# altera_digital_explorer.net
KiCad netlist of a schematic drawn in EAGLE
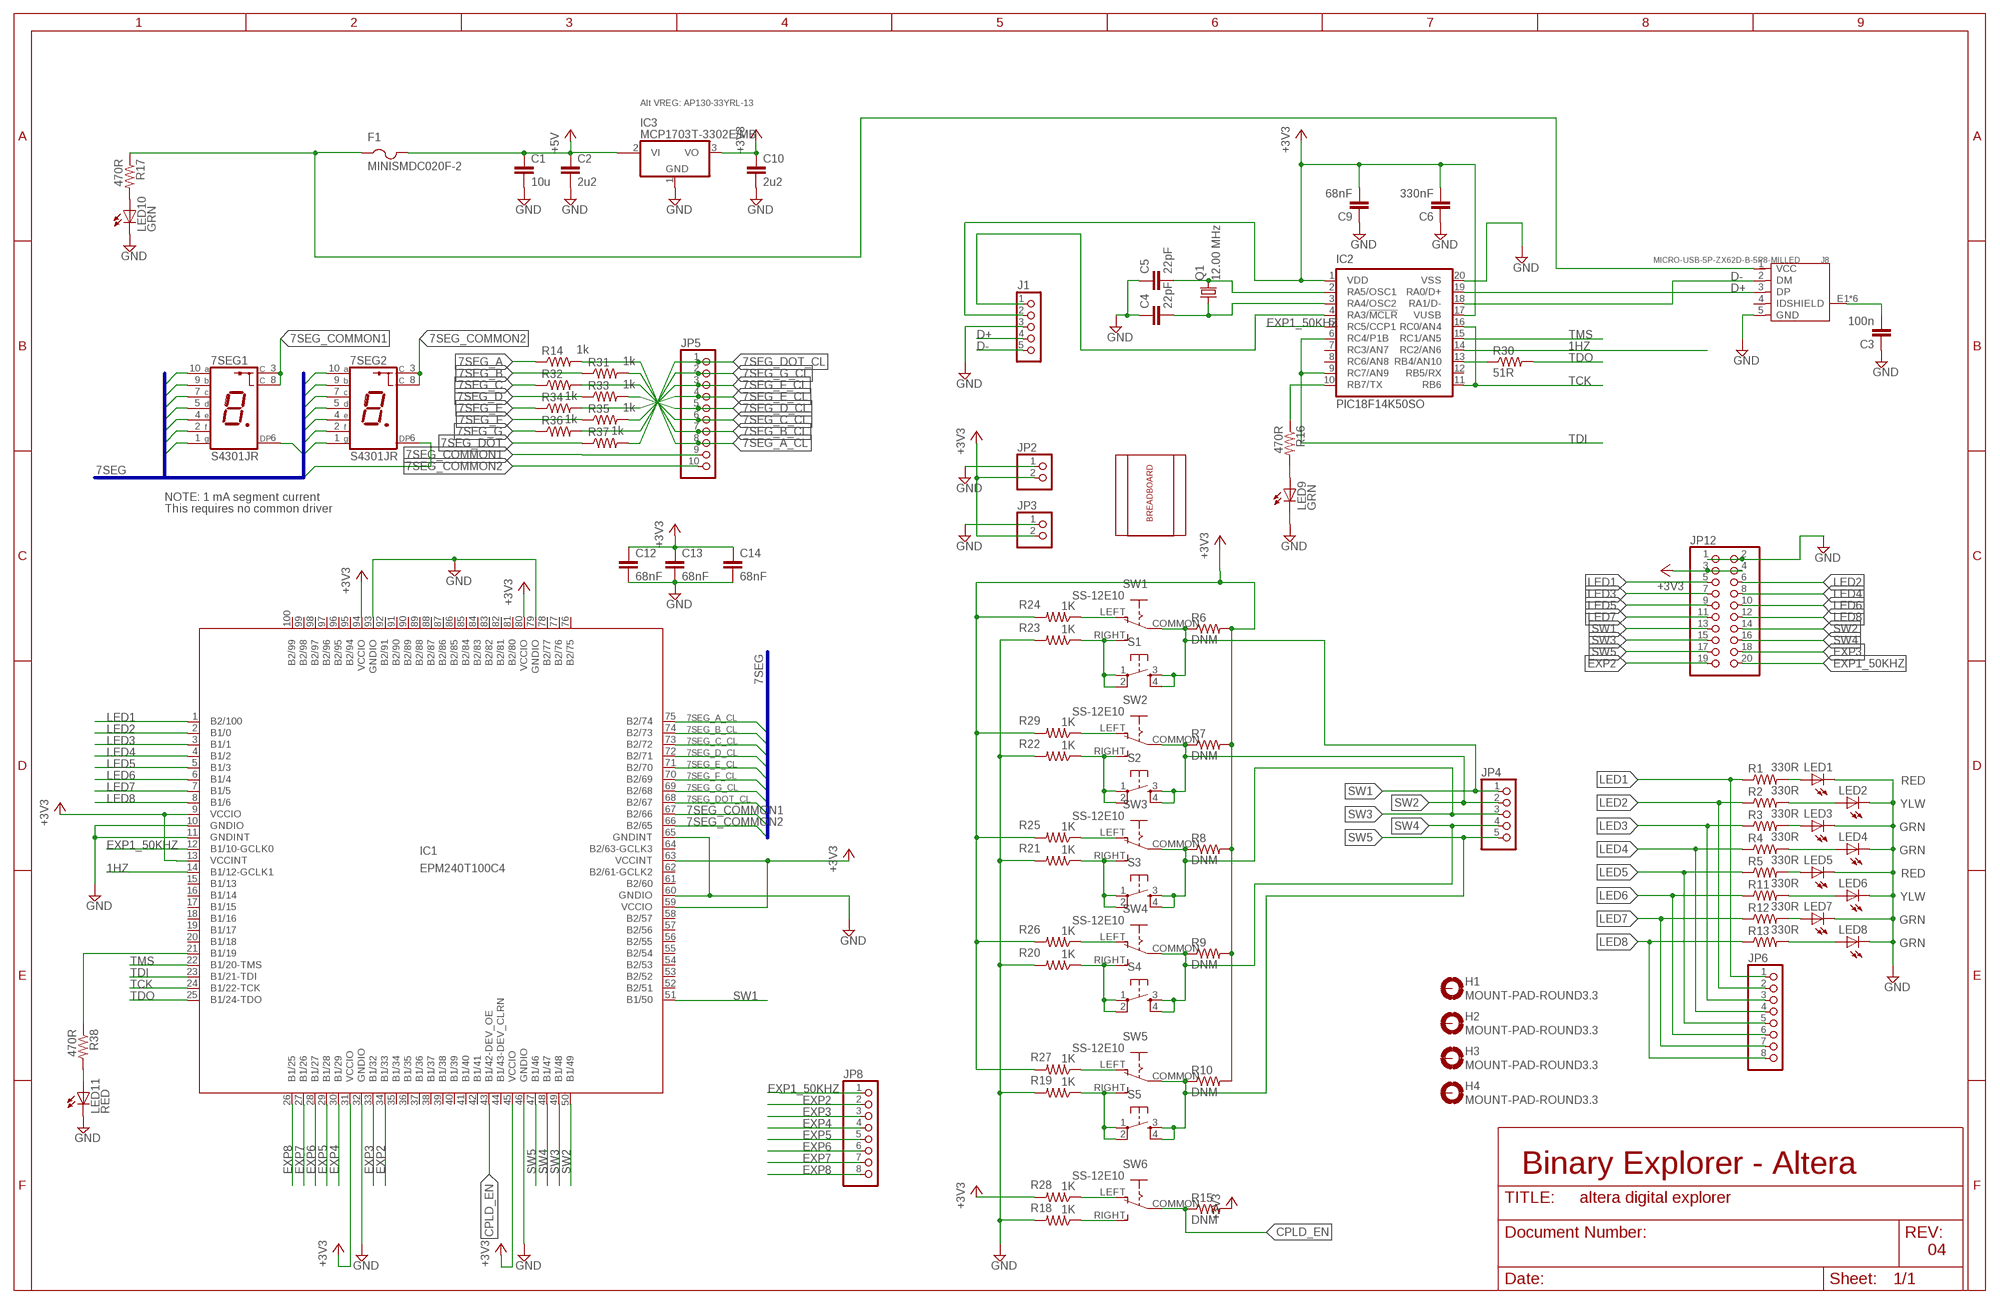
[diagram p0: schematic, sheet 1]

(export (version "E")
  (design (tool "Eeschema 10.0.6"))
  (components
    (comp (ref "7SEG1")
      (value "S4301JR")
      (footprint "eagle-import:S4301B")
      (libsource (lib "eagle-import") (part "S4301B"))
    )
    (comp (ref "7SEG2")
      (value "S4301JR")
      (footprint "eagle-import:S4301B")
      (libsource (lib "eagle-import") (part "S4301B"))
    )
    (comp (ref "C1")
      (value "10u")
      (footprint "eagle-import:C0805")
      (libsource (lib "eagle-import") (part "C-EUC0805"))
    )
    (comp (ref "C2")
      (value "2u2")
      (footprint "eagle-import:C0805")
      (libsource (lib "eagle-import") (part "C-EUC0805"))
    )
    (comp (ref "C3")
      (value "100n")
      (footprint "eagle-import:C0603")
      (libsource (lib "eagle-import") (part "C-EUC0603"))
    )
    (comp (ref "C4")
      (value "22pF")
      (footprint "eagle-import:C0603")
      (libsource (lib "eagle-import") (part "C-EUC0603"))
    )
    (comp (ref "C5")
      (value "22pF")
      (footprint "eagle-import:C0603")
      (libsource (lib "eagle-import") (part "C-EUC0603"))
    )
    (comp (ref "C6")
      (value "330nF")
      (footprint "eagle-import:C0603")
      (libsource (lib "eagle-import") (part "C-EUC0603"))
    )
    (comp (ref "C9")
      (value "68nF")
      (footprint "eagle-import:C0603")
      (libsource (lib "eagle-import") (part "C-EUC0603"))
    )
    (comp (ref "C10")
      (value "2u2")
      (footprint "eagle-import:C0805")
      (libsource (lib "eagle-import") (part "C-EUC0805"))
    )
    (comp (ref "C12")
      (value "68nF")
      (footprint "eagle-import:C0603")
      (libsource (lib "eagle-import") (part "resistor_C-EUC0603"))
    )
    (comp (ref "C13")
      (value "68nF")
      (footprint "eagle-import:C0603K")
      (libsource (lib "eagle-import") (part "resistor_C-EUC0603K"))
    )
    (comp (ref "C14")
      (value "68nF")
      (footprint "eagle-import:C0603")
      (libsource (lib "eagle-import") (part "resistor_C-EUC0603"))
    )
    (comp (ref "F1")
      (value "MINISMDC020F-2")
      (footprint "eagle-import:1812")
      (libsource (lib "eagle-import") (part "PTCFUSE-1812"))
    )
    (comp (ref "H1")
      (value "MOUNT-PAD-ROUND3.3")
      (footprint "eagle-import:3,3-PAD")
      (libsource (lib "eagle-import") (part "MOUNT-PAD-ROUND3.3"))
    )
    (comp (ref "H2")
      (value "MOUNT-PAD-ROUND3.3")
      (footprint "eagle-import:3,3-PAD")
      (libsource (lib "eagle-import") (part "MOUNT-PAD-ROUND3.3"))
    )
    (comp (ref "H3")
      (value "MOUNT-PAD-ROUND3.3")
      (footprint "eagle-import:3,3-PAD")
      (libsource (lib "eagle-import") (part "MOUNT-PAD-ROUND3.3"))
    )
    (comp (ref "H4")
      (value "MOUNT-PAD-ROUND3.3")
      (footprint "eagle-import:3,3-PAD")
      (libsource (lib "eagle-import") (part "MOUNT-PAD-ROUND3.3"))
    )
    (comp (ref "IC1")
      (value "EPM240T100C4")
      (footprint "eagle-import:TQFP100")
      (libsource (lib "eagle-import") (part "EPM240T100C4"))
    )
    (comp (ref "IC2")
      (value "PIC18F14K50SO")
      (footprint "eagle-import:SO20")
      (libsource (lib "eagle-import") (part "PIC18F14K50SO"))
    )
    (comp (ref "IC3")
      (value "MCP1703T-3302E/MB")
      (footprint "eagle-import:SOT89")
      (libsource (lib "eagle-import") (part "MCP1703MB33"))
    )
    (comp (ref "J1")
      (value "CON_HEADER_1X05-PTH")
      (footprint "eagle-import:M1X5")
      (libsource (lib "eagle-import") (part "CON_HEADER_1X05-PTH"))
    )
    (comp (ref "J8")
      (value "MICRO-USB-5P-ZX62D-B-5P8-MILLED")
      (footprint "eagle-import:B-SMD-5P-TH-MILLED")
      (fields (field (name "MPN") "ZX62D-B-5P8") (field (name "OC_DIGIKEY") "H11610CT-ND"))
      (libsource (lib "eagle-import") (part "MICRO-USB-5P-ZX62D-B-5P8-MILLED"))
    )
    (comp (ref "JP2")
      (value "PINHD-1X2")
      (footprint "eagle-import:1X02")
      (libsource (lib "eagle-import") (part "PINHD-1X2"))
    )
    (comp (ref "JP3")
      (value "PINHD-1X2")
      (footprint "eagle-import:1X02")
      (libsource (lib "eagle-import") (part "PINHD-1X2"))
    )
    (comp (ref "JP4")
      (value "PINHD-1X5")
      (footprint "eagle-import:1X05")
      (libsource (lib "eagle-import") (part "PINHD-1X5"))
    )
    (comp (ref "JP5")
      (value "PINHD-1X10")
      (footprint "eagle-import:1X10")
      (libsource (lib "eagle-import") (part "PINHD-1X10"))
    )
    (comp (ref "JP6")
      (value "PINHD-1X8")
      (footprint "eagle-import:1X08")
      (libsource (lib "eagle-import") (part "PINHD-1X8"))
    )
    (comp (ref "JP8")
      (value "PINHD-1X8")
      (footprint "eagle-import:1X08")
      (libsource (lib "eagle-import") (part "PINHD-1X8"))
    )
    (comp (ref "JP12")
      (value "PINHD-2X10")
      (footprint "eagle-import:2X10")
      (libsource (lib "eagle-import") (part "PINHD-2X10"))
    )
    (comp (ref "LED1")
      (value "RED")
      (footprint "eagle-import:CHIP-LED0805")
      (libsource (lib "eagle-import") (part "LEDCHIP-LED0805"))
    )
    (comp (ref "LED2")
      (value "YLW")
      (footprint "eagle-import:CHIP-LED0805")
      (libsource (lib "eagle-import") (part "LEDCHIP-LED0805"))
    )
    (comp (ref "LED3")
      (value "GRN")
      (footprint "eagle-import:CHIP-LED0805")
      (libsource (lib "eagle-import") (part "LEDCHIP-LED0805"))
    )
    (comp (ref "LED4")
      (value "GRN")
      (footprint "eagle-import:CHIP-LED0805")
      (libsource (lib "eagle-import") (part "LEDCHIP-LED0805"))
    )
    (comp (ref "LED5")
      (value "RED")
      (footprint "eagle-import:CHIP-LED0805")
      (libsource (lib "eagle-import") (part "LEDCHIP-LED0805"))
    )
    (comp (ref "LED6")
      (value "YLW")
      (footprint "eagle-import:CHIP-LED0805")
      (libsource (lib "eagle-import") (part "LEDCHIP-LED0805"))
    )
    (comp (ref "LED7")
      (value "GRN")
      (footprint "eagle-import:CHIP-LED0805")
      (libsource (lib "eagle-import") (part "LEDCHIP-LED0805"))
    )
    (comp (ref "LED8")
      (value "GRN")
      (footprint "eagle-import:CHIP-LED0805")
      (libsource (lib "eagle-import") (part "LEDCHIP-LED0805"))
    )
    (comp (ref "LED9")
      (value "GRN")
      (footprint "eagle-import:CHIP-LED0805")
      (libsource (lib "eagle-import") (part "LEDCHIP-LED0805"))
    )
    (comp (ref "LED10")
      (value "GRN")
      (footprint "eagle-import:CHIP-LED0805")
      (libsource (lib "eagle-import") (part "LEDCHIP-LED0805"))
    )
    (comp (ref "LED11")
      (value "RED")
      (footprint "eagle-import:CHIP-LED0805")
      (libsource (lib "eagle-import") (part "LEDCHIP-LED0805"))
    )
    (comp (ref "Q1")
      (value "12.00 MHz")
      (footprint "eagle-import:HC49UP")
      (fields (field (name "MPN") "ATS080BSM-1"))
      (libsource (lib "eagle-import") (part "CRYSTALHC49UP"))
    )
    (comp (ref "R1")
      (value "330R")
      (footprint "eagle-import:R0603")
      (libsource (lib "eagle-import") (part "resistor_R-US_R0603"))
    )
    (comp (ref "R2")
      (value "330R")
      (footprint "eagle-import:R0603")
      (libsource (lib "eagle-import") (part "resistor_R-US_R0603"))
    )
    (comp (ref "R3")
      (value "330R")
      (footprint "eagle-import:R0603")
      (libsource (lib "eagle-import") (part "resistor_R-US_R0603"))
    )
    (comp (ref "R4")
      (value "330R")
      (footprint "eagle-import:R0603")
      (libsource (lib "eagle-import") (part "resistor_R-US_R0603"))
    )
    (comp (ref "R5")
      (value "330R")
      (footprint "eagle-import:R0603")
      (libsource (lib "eagle-import") (part "resistor_R-US_R0603"))
    )
    (comp (ref "R6")
      (value "DNM")
      (footprint "eagle-import:R0603")
      (libsource (lib "eagle-import") (part "resistor_R-US_R0603"))
    )
    (comp (ref "R7")
      (value "DNM")
      (footprint "eagle-import:R0603")
      (libsource (lib "eagle-import") (part "resistor_R-US_R0603"))
    )
    (comp (ref "R8")
      (value "DNM")
      (footprint "eagle-import:R0603")
      (libsource (lib "eagle-import") (part "resistor_R-US_R0603"))
    )
    (comp (ref "R9")
      (value "DNM")
      (footprint "eagle-import:R0603")
      (libsource (lib "eagle-import") (part "resistor_R-US_R0603"))
    )
    (comp (ref "R10")
      (value "DNM")
      (footprint "eagle-import:R0603")
      (libsource (lib "eagle-import") (part "resistor_R-US_R0603"))
    )
    (comp (ref "R11")
      (value "330R")
      (footprint "eagle-import:R0603")
      (libsource (lib "eagle-import") (part "resistor_R-US_R0603"))
    )
    (comp (ref "R12")
      (value "330R")
      (footprint "eagle-import:R0603")
      (libsource (lib "eagle-import") (part "resistor_R-US_R0603"))
    )
    (comp (ref "R13")
      (value "330R")
      (footprint "eagle-import:R0603")
      (libsource (lib "eagle-import") (part "resistor_R-US_R0603"))
    )
    (comp (ref "R14")
      (value "1k")
      (footprint "eagle-import:R0603")
      (libsource (lib "eagle-import") (part "resistor_R-US_R0603"))
    )
    (comp (ref "R15")
      (value "DNM")
      (footprint "eagle-import:R0603")
      (libsource (lib "eagle-import") (part "resistor_R-US_R0603"))
    )
    (comp (ref "R16")
      (value "470R")
      (footprint "eagle-import:R0603")
      (libsource (lib "eagle-import") (part "R-US_R0603"))
    )
    (comp (ref "R17")
      (value "470R")
      (footprint "eagle-import:R0603")
      (libsource (lib "eagle-import") (part "R-US_R0603"))
    )
    (comp (ref "R18")
      (value "1K")
      (footprint "eagle-import:R0603")
      (libsource (lib "eagle-import") (part "resistor_R-US_R0603"))
    )
    (comp (ref "R19")
      (value "1K")
      (footprint "eagle-import:R0603")
      (libsource (lib "eagle-import") (part "resistor_R-US_R0603"))
    )
    (comp (ref "R20")
      (value "1K")
      (footprint "eagle-import:R0603")
      (libsource (lib "eagle-import") (part "resistor_R-US_R0603"))
    )
    (comp (ref "R21")
      (value "1K")
      (footprint "eagle-import:R0603")
      (libsource (lib "eagle-import") (part "resistor_R-US_R0603"))
    )
    (comp (ref "R22")
      (value "1K")
      (footprint "eagle-import:R0603")
      (libsource (lib "eagle-import") (part "resistor_R-US_R0603"))
    )
    (comp (ref "R23")
      (value "1K")
      (footprint "eagle-import:R0603")
      (libsource (lib "eagle-import") (part "resistor_R-US_R0603"))
    )
    (comp (ref "R24")
      (value "1K")
      (footprint "eagle-import:R0603")
      (libsource (lib "eagle-import") (part "resistor_R-US_R0603"))
    )
    (comp (ref "R25")
      (value "1K")
      (footprint "eagle-import:R0603")
      (libsource (lib "eagle-import") (part "resistor_R-US_R0603"))
    )
    (comp (ref "R26")
      (value "1K")
      (footprint "eagle-import:R0603")
      (libsource (lib "eagle-import") (part "resistor_R-US_R0603"))
    )
    (comp (ref "R27")
      (value "1K")
      (footprint "eagle-import:R0603")
      (libsource (lib "eagle-import") (part "resistor_R-US_R0603"))
    )
    (comp (ref "R28")
      (value "1K")
      (footprint "eagle-import:R0603")
      (libsource (lib "eagle-import") (part "resistor_R-US_R0603"))
    )
    (comp (ref "R29")
      (value "1K")
      (footprint "eagle-import:R0603")
      (libsource (lib "eagle-import") (part "resistor_R-US_R0603"))
    )
    (comp (ref "R30")
      (value "51R")
      (footprint "eagle-import:R0603")
      (libsource (lib "eagle-import") (part "R-US_R0603"))
    )
    (comp (ref "R31")
      (value "1k")
      (footprint "eagle-import:R0603")
      (libsource (lib "eagle-import") (part "resistor_R-US_R0603"))
    )
    (comp (ref "R32")
      (value "R-US_R0603")
      (footprint "eagle-import:R0603")
      (libsource (lib "eagle-import") (part "resistor_R-US_R0603"))
    )
    (comp (ref "R33")
      (value "1k")
      (footprint "eagle-import:R0603")
      (libsource (lib "eagle-import") (part "resistor_R-US_R0603"))
    )
    (comp (ref "R34")
      (value "1k")
      (footprint "eagle-import:R0603")
      (libsource (lib "eagle-import") (part "resistor_R-US_R0603"))
    )
    (comp (ref "R35")
      (value "1k")
      (footprint "eagle-import:R0603")
      (libsource (lib "eagle-import") (part "resistor_R-US_R0603"))
    )
    (comp (ref "R36")
      (value "1k")
      (footprint "eagle-import:R0603")
      (libsource (lib "eagle-import") (part "resistor_R-US_R0603"))
    )
    (comp (ref "R37")
      (value "1k")
      (footprint "eagle-import:R0603")
      (libsource (lib "eagle-import") (part "resistor_R-US_R0603"))
    )
    (comp (ref "R38")
      (value "470R")
      (footprint "eagle-import:R0603")
      (libsource (lib "eagle-import") (part "R-US_R0603"))
    )
    (comp (ref "S1")
      (value "TAC_SWITCHPTH")
      (footprint "eagle-import:TACTILE-PTH")
      (libsource (lib "eagle-import") (part "TAC_SWITCHPTH"))
    )
    (comp (ref "S2")
      (value "TAC_SWITCHPTH")
      (footprint "eagle-import:TACTILE-PTH")
      (libsource (lib "eagle-import") (part "TAC_SWITCHPTH"))
    )
    (comp (ref "S3")
      (value "TAC_SWITCHPTH")
      (footprint "eagle-import:TACTILE-PTH")
      (libsource (lib "eagle-import") (part "TAC_SWITCHPTH"))
    )
    (comp (ref "S4")
      (value "TAC_SWITCHPTH")
      (footprint "eagle-import:TACTILE-PTH")
      (libsource (lib "eagle-import") (part "TAC_SWITCHPTH"))
    )
    (comp (ref "S5")
      (value "TAC_SWITCHPTH")
      (footprint "eagle-import:TACTILE-PTH")
      (libsource (lib "eagle-import") (part "TAC_SWITCHPTH"))
    )
    (comp (ref "SW1")
      (value "SS-12E10")
      (footprint "eagle-import:SS-12E10")
      (libsource (lib "eagle-import") (part "SS-12E10"))
    )
    (comp (ref "SW2")
      (value "SS-12E10")
      (footprint "eagle-import:SS-12E10")
      (libsource (lib "eagle-import") (part "SS-12E10"))
    )
    (comp (ref "SW3")
      (value "SS-12E10")
      (footprint "eagle-import:SS-12E10")
      (libsource (lib "eagle-import") (part "SS-12E10"))
    )
    (comp (ref "SW4")
      (value "SS-12E10")
      (footprint "eagle-import:SS-12E10")
      (libsource (lib "eagle-import") (part "SS-12E10"))
    )
    (comp (ref "SW5")
      (value "SS-12E10")
      (footprint "eagle-import:SS-12E10")
      (libsource (lib "eagle-import") (part "SS-12E10"))
    )
    (comp (ref "SW6")
      (value "SS-12E10")
      (footprint "eagle-import:SS-12E10")
      (libsource (lib "eagle-import") (part "SS-12E10"))
    )
    (comp (ref "U$1")
      (value "BB-400TP")
      (footprint "eagle-import:BB-400TP")
      (libsource (lib "eagle-import") (part "BB-400TP"))
    )
  )
  (nets
    (net (code "1") (name "+3V3") (class "Default")
      (node (ref "C10") (pin "1") (pinfunction "1_1") (pintype "passive"))
      (node (ref "C12") (pin "1") (pinfunction "1_1") (pintype "passive"))
      (node (ref "C13") (pin "1") (pinfunction "1_1") (pintype "passive"))
      (node (ref "C14") (pin "1") (pinfunction "1_1") (pintype "passive"))
      (node (ref "C6") (pin "2") (pinfunction "2_2") (pintype "passive"))
      (node (ref "C9") (pin "2") (pinfunction "2_2") (pintype "passive"))
      (node (ref "IC1") (pin "13") (pinfunction "VCCINT_13") (pintype "power_in"))
      (node (ref "IC1") (pin "31") (pinfunction "VCCIO_31") (pintype "power_in"))
      (node (ref "IC1") (pin "45") (pinfunction "VCCIO_45") (pintype "power_in"))
      (node (ref "IC1") (pin "59") (pinfunction "VCCIO_59") (pintype "power_in"))
      (node (ref "IC1") (pin "63") (pinfunction "VCCINT_63") (pintype "power_in"))
      (node (ref "IC1") (pin "80") (pinfunction "VCCIO_80") (pintype "power_in"))
      (node (ref "IC1") (pin "9") (pinfunction "VCCIO_9") (pintype "power_in"))
      (node (ref "IC1") (pin "94") (pinfunction "VCCIO_94") (pintype "power_in"))
      (node (ref "IC2") (pin "1") (pinfunction "VDD_1") (pintype "power_in"))
      (node (ref "IC2") (pin "17") (pinfunction "VUSB_17") (pintype "bidirectional"))
      (node (ref "IC3") (pin "3") (pinfunction "VO_3") (pintype "passive"))
      (node (ref "J1") (pin "2") (pinfunction "2_2") (pintype "bidirectional"))
      (node (ref "JP12") (pin "3") (pinfunction "3_3") (pintype "passive"))
      (node (ref "JP12") (pin "4") (pinfunction "4_4") (pintype "passive"))
      (node (ref "JP2") (pin "2") (pinfunction "2_2") (pintype "passive"))
      (node (ref "JP3") (pin "2") (pinfunction "2_2") (pintype "passive"))
      (node (ref "R10") (pin "2") (pinfunction "2_2") (pintype "passive"))
      (node (ref "R15") (pin "2") (pinfunction "2_2") (pintype "passive"))
      (node (ref "R24") (pin "2") (pinfunction "2_2") (pintype "passive"))
      (node (ref "R25") (pin "2") (pinfunction "2_2") (pintype "passive"))
      (node (ref "R26") (pin "2") (pinfunction "2_2") (pintype "passive"))
      (node (ref "R27") (pin "2") (pinfunction "2_2") (pintype "passive"))
      (node (ref "R28") (pin "2") (pinfunction "2_2") (pintype "passive"))
      (node (ref "R29") (pin "2") (pinfunction "2_2") (pintype "passive"))
      (node (ref "R6") (pin "2") (pinfunction "2_2") (pintype "passive"))
      (node (ref "R7") (pin "2") (pinfunction "2_2") (pintype "passive"))
      (node (ref "R8") (pin "2") (pinfunction "2_2") (pintype "passive"))
      (node (ref "R9") (pin "2") (pinfunction "2_2") (pintype "passive"))
    )
    (net (code "2") (name "+5V") (class "Default")
      (node (ref "C1") (pin "1") (pinfunction "1_1") (pintype "passive"))
      (node (ref "C2") (pin "1") (pinfunction "1_1") (pintype "passive"))
      (node (ref "F1") (pin "2") (pinfunction "2_2") (pintype "passive"))
      (node (ref "IC3") (pin "2@1") (pinfunction "VI1_2@1") (pintype "input"))
    )
    (net (code "3") (name "/1HZ") (class "Default")
      (node (ref "IC1") (pin "14") (pinfunction "B1/12-GCLK1_14") (pintype "bidirectional"))
      (node (ref "IC2") (pin "14") (pinfunction "RC2/AN6_14") (pintype "bidirectional"))
    )
    (net (code "4") (name "/D+") (class "Default")
      (node (ref "IC2") (pin "19") (pinfunction "RA0/D+_19") (pintype "bidirectional"))
      (node (ref "J1") (pin "4") (pinfunction "4_4") (pintype "bidirectional"))
      (node (ref "J8") (pin "3") (pinfunction "DP_3") (pintype "bidirectional"))
    )
    (net (code "5") (name "/D-") (class "Default")
      (node (ref "IC2") (pin "18") (pinfunction "RA1/D-_18") (pintype "bidirectional"))
      (node (ref "J1") (pin "5") (pinfunction "5_5") (pintype "bidirectional"))
      (node (ref "J8") (pin "2") (pinfunction "DM_2") (pintype "bidirectional"))
    )
    (net (code "6") (name "/EXP4") (class "Default")
      (node (ref "IC1") (pin "30") (pinfunction "B1/29_30") (pintype "bidirectional"))
      (node (ref "JP8") (pin "4") (pinfunction "4_4") (pintype "passive"))
    )
    (net (code "7") (name "/EXP5") (class "Default")
      (node (ref "IC1") (pin "29") (pinfunction "B1/28_29") (pintype "bidirectional"))
      (node (ref "JP8") (pin "5") (pinfunction "5_5") (pintype "passive"))
    )
    (net (code "8") (name "/EXP6") (class "Default")
      (node (ref "IC1") (pin "28") (pinfunction "B1/27_28") (pintype "bidirectional"))
      (node (ref "JP8") (pin "6") (pinfunction "6_6") (pintype "passive"))
    )
    (net (code "9") (name "/EXP7") (class "Default")
      (node (ref "IC1") (pin "27") (pinfunction "B1/26_27") (pintype "bidirectional"))
      (node (ref "JP8") (pin "7") (pinfunction "7_7") (pintype "passive"))
    )
    (net (code "10") (name "/EXP8") (class "Default")
      (node (ref "IC1") (pin "26") (pinfunction "B1/25_26") (pintype "bidirectional"))
      (node (ref "JP8") (pin "8") (pinfunction "8_8") (pintype "passive"))
    )
    (net (code "11") (name "/TCK") (class "Default")
      (node (ref "IC1") (pin "24") (pinfunction "B1/22-TCK_24") (pintype "input"))
      (node (ref "IC2") (pin "11") (pinfunction "RB6_11") (pintype "bidirectional"))
      (node (ref "IC2") (pin "16") (pinfunction "RC0/AN4_16") (pintype "bidirectional"))
    )
    (net (code "12") (name "/TDI") (class "Default")
      (node (ref "IC1") (pin "23") (pinfunction "B1/21-TDI_23") (pintype "input"))
      (node (ref "IC2") (pin "6") (pinfunction "RC4/P1B_6") (pintype "bidirectional"))
      (node (ref "IC2") (pin "9") (pinfunction "RC7/AN9_9") (pintype "bidirectional"))
    )
    (net (code "13") (name "/TDO") (class "Default")
      (node (ref "IC1") (pin "25") (pinfunction "B1/24-TDO_25") (pintype "output"))
      (node (ref "R30") (pin "2") (pinfunction "2_2") (pintype "passive"))
    )
    (net (code "14") (name "/TMS") (class "Default")
      (node (ref "IC1") (pin "22") (pinfunction "B1/20-TMS_22") (pintype "input"))
      (node (ref "IC2") (pin "15") (pinfunction "RC1/AN5_15") (pintype "bidirectional"))
    )
    (net (code "15") (name "7SEG_A") (class "Default")
      (node (ref "7SEG1") (pin "10") (pinfunction "A_10") (pintype "passive"))
      (node (ref "7SEG2") (pin "10") (pinfunction "A_10") (pintype "passive"))
      (node (ref "R14") (pin "1") (pinfunction "1_1") (pintype "passive"))
    )
    (net (code "16") (name "7SEG_A_CL") (class "Default")
      (node (ref "IC1") (pin "75") (pinfunction "B2/74_75") (pintype "bidirectional"))
      (node (ref "JP5") (pin "8") (pinfunction "8_8") (pintype "passive"))
      (node (ref "R14") (pin "2") (pinfunction "2_2") (pintype "passive"))
    )
    (net (code "17") (name "7SEG_B") (class "Default")
      (node (ref "7SEG1") (pin "9") (pinfunction "B_9") (pintype "passive"))
      (node (ref "7SEG2") (pin "9") (pinfunction "B_9") (pintype "passive"))
      (node (ref "R31") (pin "1") (pinfunction "1_1") (pintype "passive"))
    )
    (net (code "18") (name "7SEG_B_CL") (class "Default")
      (node (ref "IC1") (pin "74") (pinfunction "B2/73_74") (pintype "bidirectional"))
      (node (ref "JP5") (pin "7") (pinfunction "7_7") (pintype "passive"))
      (node (ref "R31") (pin "2") (pinfunction "2_2") (pintype "passive"))
    )
    (net (code "19") (name "7SEG_C") (class "Default")
      (node (ref "7SEG1") (pin "7") (pinfunction "C_7") (pintype "passive"))
      (node (ref "7SEG2") (pin "7") (pinfunction "C_7") (pintype "passive"))
      (node (ref "R32") (pin "1") (pinfunction "1_1") (pintype "passive"))
    )
    (net (code "20") (name "7SEG_COMMON1") (class "Default")
      (node (ref "7SEG1") (pin "3") (pinfunction "C_3") (pintype "passive"))
      (node (ref "7SEG1") (pin "8") (pinfunction "C_8") (pintype "passive"))
      (node (ref "IC1") (pin "67") (pinfunction "B2/66_67") (pintype "bidirectional"))
      (node (ref "JP5") (pin "9") (pinfunction "9_9") (pintype "passive"))
    )
    (net (code "21") (name "7SEG_COMMON2") (class "Default")
      (node (ref "7SEG2") (pin "3") (pinfunction "C_3") (pintype "passive"))
      (node (ref "7SEG2") (pin "8") (pinfunction "C_8") (pintype "passive"))
      (node (ref "IC1") (pin "66") (pinfunction "B2/65_66") (pintype "bidirectional"))
      (node (ref "JP5") (pin "10") (pinfunction "10_10") (pintype "passive"))
    )
    (net (code "22") (name "7SEG_C_CL") (class "Default")
      (node (ref "IC1") (pin "73") (pinfunction "B2/72_73") (pintype "bidirectional"))
      (node (ref "JP5") (pin "6") (pinfunction "6_6") (pintype "passive"))
      (node (ref "R32") (pin "2") (pinfunction "2_2") (pintype "passive"))
    )
    (net (code "23") (name "7SEG_D") (class "Default")
      (node (ref "7SEG1") (pin "5") (pinfunction "D_5") (pintype "passive"))
      (node (ref "7SEG2") (pin "5") (pinfunction "D_5") (pintype "passive"))
      (node (ref "R33") (pin "1") (pinfunction "1_1") (pintype "passive"))
    )
    (net (code "24") (name "7SEG_DOT") (class "Default")
      (node (ref "7SEG1") (pin "6") (pinfunction "DP_6") (pintype "passive"))
      (node (ref "7SEG2") (pin "6") (pinfunction "DP_6") (pintype "passive"))
      (node (ref "R37") (pin "1") (pinfunction "1_1") (pintype "passive"))
    )
    (net (code "25") (name "7SEG_DOT_CL") (class "Default")
      (node (ref "IC1") (pin "68") (pinfunction "B2/67_68") (pintype "bidirectional"))
      (node (ref "JP5") (pin "1") (pinfunction "1_1") (pintype "passive"))
      (node (ref "R37") (pin "2") (pinfunction "2_2") (pintype "passive"))
    )
    (net (code "26") (name "7SEG_D_CL") (class "Default")
      (node (ref "IC1") (pin "72") (pinfunction "B2/71_72") (pintype "bidirectional"))
      (node (ref "JP5") (pin "5") (pinfunction "5_5") (pintype "passive"))
      (node (ref "R33") (pin "2") (pinfunction "2_2") (pintype "passive"))
    )
    (net (code "27") (name "7SEG_E") (class "Default")
      (node (ref "7SEG1") (pin "4") (pinfunction "E_4") (pintype "passive"))
      (node (ref "7SEG2") (pin "4") (pinfunction "E_4") (pintype "passive"))
      (node (ref "R34") (pin "1") (pinfunction "1_1") (pintype "passive"))
    )
    (net (code "28") (name "7SEG_E_CL") (class "Default")
      (node (ref "IC1") (pin "71") (pinfunction "B2/70_71") (pintype "bidirectional"))
      (node (ref "JP5") (pin "4") (pinfunction "4_4") (pintype "passive"))
      (node (ref "R34") (pin "2") (pinfunction "2_2") (pintype "passive"))
    )
    (net (code "29") (name "7SEG_F") (class "Default")
      (node (ref "7SEG1") (pin "2") (pinfunction "F_2") (pintype "passive"))
      (node (ref "7SEG2") (pin "2") (pinfunction "F_2") (pintype "passive"))
      (node (ref "R35") (pin "1") (pinfunction "1_1") (pintype "passive"))
    )
    (net (code "30") (name "7SEG_F_CL") (class "Default")
      (node (ref "IC1") (pin "70") (pinfunction "B2/69_70") (pintype "bidirectional"))
      (node (ref "JP5") (pin "3") (pinfunction "3_3") (pintype "passive"))
      (node (ref "R35") (pin "2") (pinfunction "2_2") (pintype "passive"))
    )
    (net (code "31") (name "7SEG_G") (class "Default")
      (node (ref "7SEG1") (pin "1") (pinfunction "G_1") (pintype "passive"))
      (node (ref "7SEG2") (pin "1") (pinfunction "G_1") (pintype "passive"))
      (node (ref "R36") (pin "1") (pinfunction "1_1") (pintype "passive"))
    )
    (net (code "32") (name "7SEG_G_CL") (class "Default")
      (node (ref "IC1") (pin "69") (pinfunction "B2/68_69") (pintype "bidirectional"))
      (node (ref "JP5") (pin "2") (pinfunction "2_2") (pintype "passive"))
      (node (ref "R36") (pin "2") (pinfunction "2_2") (pintype "passive"))
    )
    (net (code "33") (name "CPLD_EN") (class "Default")
      (node (ref "IC1") (pin "43") (pinfunction "B1/42-DEV_OE_43") (pintype "bidirectional"))
      (node (ref "R15") (pin "1") (pinfunction "1_1") (pintype "passive"))
      (node (ref "SW6") (pin "COMMON") (pinfunction "P_COMMON") (pintype "passive"))
    )
    (net (code "34") (name "EXP1_50KHZ") (class "Default")
      (node (ref "IC1") (pin "12") (pinfunction "B1/10-GCLK0_12") (pintype "bidirectional"))
      (node (ref "IC2") (pin "5") (pinfunction "RC5/CCP1_5") (pintype "bidirectional"))
      (node (ref "JP12") (pin "20") (pinfunction "20_20") (pintype "passive"))
      (node (ref "JP8") (pin "1") (pinfunction "1_1") (pintype "passive"))
    )
    (net (code "35") (name "EXP2") (class "Default")
      (node (ref "IC1") (pin "34") (pinfunction "B1/33_34") (pintype "bidirectional"))
      (node (ref "JP12") (pin "19") (pinfunction "19_19") (pintype "passive"))
      (node (ref "JP8") (pin "2") (pinfunction "2_2") (pintype "passive"))
    )
    (net (code "36") (name "EXP3") (class "Default")
      (node (ref "IC1") (pin "33") (pinfunction "B1/32_33") (pintype "bidirectional"))
      (node (ref "JP12") (pin "18") (pinfunction "18_18") (pintype "passive"))
      (node (ref "JP8") (pin "3") (pinfunction "3_3") (pintype "passive"))
    )
    (net (code "37") (name "GND") (class "Default")
      (node (ref "C1") (pin "2") (pinfunction "2_2") (pintype "passive"))
      (node (ref "C10") (pin "2") (pinfunction "2_2") (pintype "passive"))
      (node (ref "C12") (pin "2") (pinfunction "2_2") (pintype "passive"))
      (node (ref "C13") (pin "2") (pinfunction "2_2") (pintype "passive"))
      (node (ref "C14") (pin "2") (pinfunction "2_2") (pintype "passive"))
      (node (ref "C2") (pin "2") (pinfunction "2_2") (pintype "passive"))
      (node (ref "C3") (pin "1") (pinfunction "1_1") (pintype "passive"))
      (node (ref "C4") (pin "1") (pinfunction "1_1") (pintype "passive"))
      (node (ref "C5") (pin "1") (pinfunction "1_1") (pintype "passive"))
      (node (ref "C6") (pin "1") (pinfunction "1_1") (pintype "passive"))
      (node (ref "C9") (pin "1") (pinfunction "1_1") (pintype "passive"))
      (node (ref "IC1") (pin "10") (pinfunction "GNDIO_10") (pintype "power_in"))
      (node (ref "IC1") (pin "11") (pinfunction "GNDINT_11") (pintype "power_in"))
      (node (ref "IC1") (pin "32") (pinfunction "GNDIO_32") (pintype "power_in"))
      (node (ref "IC1") (pin "46") (pinfunction "GNDIO_46") (pintype "power_in"))
      (node (ref "IC1") (pin "60") (pinfunction "GNDIO_60") (pintype "power_in"))
      (node (ref "IC1") (pin "65") (pinfunction "GNDINT_65") (pintype "power_in"))
      (node (ref "IC1") (pin "79") (pinfunction "GNDIO_79") (pintype "power_in"))
      (node (ref "IC1") (pin "93") (pinfunction "GNDIO_93") (pintype "power_in"))
      (node (ref "IC2") (pin "20") (pinfunction "VSS_20") (pintype "power_in"))
      (node (ref "IC3") (pin "1") (pinfunction "GND_1") (pintype "passive"))
      (node (ref "J1") (pin "3") (pinfunction "3_3") (pintype "bidirectional"))
      (node (ref "J8") (pin "5") (pinfunction "GND_5") (pintype "bidirectional"))
      (node (ref "JP12") (pin "1") (pinfunction "1_1") (pintype "passive"))
      (node (ref "JP12") (pin "2") (pinfunction "2_2") (pintype "passive"))
      (node (ref "JP2") (pin "1") (pinfunction "1_1") (pintype "passive"))
      (node (ref "JP3") (pin "1") (pinfunction "1_1") (pintype "passive"))
      (node (ref "LED1") (pin "C") (pinfunction "C_C") (pintype "passive"))
      (node (ref "LED10") (pin "C") (pinfunction "C_C") (pintype "passive"))
      (node (ref "LED11") (pin "C") (pinfunction "C_C") (pintype "passive"))
      (node (ref "LED2") (pin "C") (pinfunction "C_C") (pintype "passive"))
      (node (ref "LED3") (pin "C") (pinfunction "C_C") (pintype "passive"))
      (node (ref "LED4") (pin "C") (pinfunction "C_C") (pintype "passive"))
      (node (ref "LED5") (pin "C") (pinfunction "C_C") (pintype "passive"))
      (node (ref "LED6") (pin "C") (pinfunction "C_C") (pintype "passive"))
      (node (ref "LED7") (pin "C") (pinfunction "C_C") (pintype "passive"))
      (node (ref "LED8") (pin "C") (pinfunction "C_C") (pintype "passive"))
      (node (ref "LED9") (pin "C") (pinfunction "C_C") (pintype "passive"))
      (node (ref "R18") (pin "2") (pinfunction "2_2") (pintype "passive"))
      (node (ref "R19") (pin "2") (pinfunction "2_2") (pintype "passive"))
      (node (ref "R20") (pin "2") (pinfunction "2_2") (pintype "passive"))
      (node (ref "R21") (pin "2") (pinfunction "2_2") (pintype "passive"))
      (node (ref "R22") (pin "2") (pinfunction "2_2") (pintype "passive"))
      (node (ref "R23") (pin "2") (pinfunction "2_2") (pintype "passive"))
    )
    (net (code "38") (name "LED1") (class "Default")
      (node (ref "IC1") (pin "1") (pinfunction "B2/100_1") (pintype "bidirectional"))
      (node (ref "JP12") (pin "5") (pinfunction "5_5") (pintype "passive"))
      (node (ref "JP6") (pin "1") (pinfunction "1_1") (pintype "passive"))
      (node (ref "R1") (pin "1") (pinfunction "1_1") (pintype "passive"))
    )
    (net (code "39") (name "LED2") (class "Default")
      (node (ref "IC1") (pin "2") (pinfunction "B1/0_2") (pintype "bidirectional"))
      (node (ref "JP12") (pin "6") (pinfunction "6_6") (pintype "passive"))
      (node (ref "JP6") (pin "2") (pinfunction "2_2") (pintype "passive"))
      (node (ref "R2") (pin "1") (pinfunction "1_1") (pintype "passive"))
    )
    (net (code "40") (name "LED3") (class "Default")
      (node (ref "IC1") (pin "3") (pinfunction "B1/1_3") (pintype "bidirectional"))
      (node (ref "JP12") (pin "7") (pinfunction "7_7") (pintype "passive"))
      (node (ref "JP6") (pin "3") (pinfunction "3_3") (pintype "passive"))
      (node (ref "R3") (pin "1") (pinfunction "1_1") (pintype "passive"))
    )
    (net (code "41") (name "LED4") (class "Default")
      (node (ref "IC1") (pin "4") (pinfunction "B1/2_4") (pintype "bidirectional"))
      (node (ref "JP12") (pin "8") (pinfunction "8_8") (pintype "passive"))
      (node (ref "JP6") (pin "4") (pinfunction "4_4") (pintype "passive"))
      (node (ref "R4") (pin "1") (pinfunction "1_1") (pintype "passive"))
    )
    (net (code "42") (name "LED5") (class "Default")
      (node (ref "IC1") (pin "5") (pinfunction "B1/3_5") (pintype "bidirectional"))
      (node (ref "JP12") (pin "9") (pinfunction "9_9") (pintype "passive"))
      (node (ref "JP6") (pin "5") (pinfunction "5_5") (pintype "passive"))
      (node (ref "R5") (pin "1") (pinfunction "1_1") (pintype "passive"))
    )
    (net (code "43") (name "LED6") (class "Default")
      (node (ref "IC1") (pin "6") (pinfunction "B1/4_6") (pintype "bidirectional"))
      (node (ref "JP12") (pin "10") (pinfunction "10_10") (pintype "passive"))
      (node (ref "JP6") (pin "6") (pinfunction "6_6") (pintype "passive"))
      (node (ref "R11") (pin "1") (pinfunction "1_1") (pintype "passive"))
    )
    (net (code "44") (name "LED7") (class "Default")
      (node (ref "IC1") (pin "7") (pinfunction "B1/5_7") (pintype "bidirectional"))
      (node (ref "JP12") (pin "11") (pinfunction "11_11") (pintype "passive"))
      (node (ref "JP6") (pin "7") (pinfunction "7_7") (pintype "passive"))
      (node (ref "R12") (pin "1") (pinfunction "1_1") (pintype "passive"))
    )
    (net (code "45") (name "LED8") (class "Default")
      (node (ref "IC1") (pin "8") (pinfunction "B1/6_8") (pintype "bidirectional"))
      (node (ref "JP12") (pin "12") (pinfunction "12_12") (pintype "passive"))
      (node (ref "JP6") (pin "8") (pinfunction "8_8") (pintype "passive"))
      (node (ref "R13") (pin "1") (pinfunction "1_1") (pintype "passive"))
    )
    (net (code "46") (name "Net-(C3-Pad2)") (class "Default")
      (node (ref "C3") (pin "2") (pinfunction "2_2") (pintype "passive"))
      (node (ref "J8") (pin "E1") (pinfunction "SHIELD_E1") (pintype "bidirectional"))
      (node (ref "J8") (pin "E2") (pinfunction "SHIELD_E2") (pintype "bidirectional"))
      (node (ref "J8") (pin "P$1") (pinfunction "SHIELD_P$1") (pintype "bidirectional"))
      (node (ref "J8") (pin "P$2") (pinfunction "SHIELD_P$2") (pintype "bidirectional"))
      (node (ref "J8") (pin "P$3") (pinfunction "SHIELD_P$3") (pintype "bidirectional"))
      (node (ref "J8") (pin "P$4") (pinfunction "SHIELD_P$4") (pintype "bidirectional"))
    )
    (net (code "47") (name "Net-(IC1-B1{slash}19)") (class "Default")
      (node (ref "IC1") (pin "21") (pinfunction "B1/19_21") (pintype "bidirectional"))
      (node (ref "R38") (pin "1") (pinfunction "1_1") (pintype "passive"))
    )
    (net (code "48") (name "Net-(IC2-RA3{slash}~{MCLR})") (class "Default")
      (node (ref "IC2") (pin "4") (pinfunction "RA3/~{MCLR}_4") (pintype "bidirectional"))
      (node (ref "J1") (pin "1") (pinfunction "1_1") (pintype "bidirectional"))
    )
    (net (code "49") (name "Net-(IC2-RA4{slash}OSC2)") (class "Default")
      (node (ref "C4") (pin "2") (pinfunction "2_2") (pintype "passive"))
      (node (ref "IC2") (pin "3") (pinfunction "RA4/OSC2_3") (pintype "bidirectional"))
      (node (ref "Q1") (pin "1") (pinfunction "1_1") (pintype "passive"))
    )
    (net (code "50") (name "Net-(IC2-RA5{slash}OSC1)") (class "Default")
      (node (ref "C5") (pin "2") (pinfunction "2_2") (pintype "passive"))
      (node (ref "IC2") (pin "2") (pinfunction "RA5/OSC1_2") (pintype "bidirectional"))
      (node (ref "Q1") (pin "2") (pinfunction "2_2") (pintype "passive"))
    )
    (net (code "51") (name "Net-(IC2-RB4{slash}AN10)") (class "Default")
      (node (ref "IC2") (pin "13") (pinfunction "RB4/AN10_13") (pintype "bidirectional"))
      (node (ref "R30") (pin "1") (pinfunction "1_1") (pintype "passive"))
    )
    (net (code "52") (name "Net-(IC2-RB7{slash}TX)") (class "Default")
      (node (ref "IC2") (pin "10") (pinfunction "RB7/TX_10") (pintype "bidirectional"))
      (node (ref "R16") (pin "1") (pinfunction "1_1") (pintype "passive"))
    )
    (net (code "53") (name "Net-(J8-VCC)") (class "Default")
      (node (ref "F1") (pin "1") (pinfunction "1_1") (pintype "passive"))
      (node (ref "J8") (pin "1") (pinfunction "VCC_1") (pintype "bidirectional"))
      (node (ref "R17") (pin "1") (pinfunction "1_1") (pintype "passive"))
    )
    (net (code "54") (name "Net-(LED1-PadA)") (class "Default")
      (node (ref "LED1") (pin "A") (pinfunction "A_A") (pintype "passive"))
      (node (ref "R1") (pin "2") (pinfunction "2_2") (pintype "passive"))
    )
    (net (code "55") (name "Net-(LED2-PadA)") (class "Default")
      (node (ref "LED2") (pin "A") (pinfunction "A_A") (pintype "passive"))
      (node (ref "R2") (pin "2") (pinfunction "2_2") (pintype "passive"))
    )
    (net (code "56") (name "Net-(LED3-PadA)") (class "Default")
      (node (ref "LED3") (pin "A") (pinfunction "A_A") (pintype "passive"))
      (node (ref "R3") (pin "2") (pinfunction "2_2") (pintype "passive"))
    )
    (net (code "57") (name "Net-(LED4-PadA)") (class "Default")
      (node (ref "LED4") (pin "A") (pinfunction "A_A") (pintype "passive"))
      (node (ref "R4") (pin "2") (pinfunction "2_2") (pintype "passive"))
    )
    (net (code "58") (name "Net-(LED5-PadA)") (class "Default")
      (node (ref "LED5") (pin "A") (pinfunction "A_A") (pintype "passive"))
      (node (ref "R5") (pin "2") (pinfunction "2_2") (pintype "passive"))
    )
    (net (code "59") (name "Net-(LED6-PadA)") (class "Default")
      (node (ref "LED6") (pin "A") (pinfunction "A_A") (pintype "passive"))
      (node (ref "R11") (pin "2") (pinfunction "2_2") (pintype "passive"))
    )
    (net (code "60") (name "Net-(LED7-PadA)") (class "Default")
      (node (ref "LED7") (pin "A") (pinfunction "A_A") (pintype "passive"))
      (node (ref "R12") (pin "2") (pinfunction "2_2") (pintype "passive"))
    )
    (net (code "61") (name "Net-(LED8-PadA)") (class "Default")
      (node (ref "LED8") (pin "A") (pinfunction "A_A") (pintype "passive"))
      (node (ref "R13") (pin "2") (pinfunction "2_2") (pintype "passive"))
    )
    (net (code "62") (name "Net-(LED9-PadA)") (class "Default")
      (node (ref "LED9") (pin "A") (pinfunction "A_A") (pintype "passive"))
      (node (ref "R16") (pin "2") (pinfunction "2_2") (pintype "passive"))
    )
    (net (code "63") (name "Net-(LED10-PadA)") (class "Default")
      (node (ref "LED10") (pin "A") (pinfunction "A_A") (pintype "passive"))
      (node (ref "R17") (pin "2") (pinfunction "2_2") (pintype "passive"))
    )
    (net (code "64") (name "Net-(LED11-PadA)") (class "Default")
      (node (ref "LED11") (pin "A") (pinfunction "A_A") (pintype "passive"))
      (node (ref "R38") (pin "2") (pinfunction "2_2") (pintype "passive"))
    )
    (net (code "65") (name "Net-(SW1-O)") (class "Default")
      (node (ref "R24") (pin "1") (pinfunction "1_1") (pintype "passive"))
      (node (ref "SW1") (pin "LEFT") (pinfunction "O_LEFT") (pintype "passive"))
    )
    (net (code "66") (name "Net-(SW1-S)") (class "Default")
      (node (ref "R23") (pin "1") (pinfunction "1_1") (pintype "passive"))
      (node (ref "S1") (pin "1") (pinfunction "1_1") (pintype "passive"))
      (node (ref "S1") (pin "2") (pinfunction "2_2") (pintype "passive"))
      (node (ref "SW1") (pin "RIGHT") (pinfunction "S_RIGHT") (pintype "passive"))
    )
    (net (code "67") (name "Net-(SW2-O)") (class "Default")
      (node (ref "R29") (pin "1") (pinfunction "1_1") (pintype "passive"))
      (node (ref "SW2") (pin "LEFT") (pinfunction "O_LEFT") (pintype "passive"))
    )
    (net (code "68") (name "Net-(SW2-S)") (class "Default")
      (node (ref "R22") (pin "1") (pinfunction "1_1") (pintype "passive"))
      (node (ref "S2") (pin "1") (pinfunction "1_1") (pintype "passive"))
      (node (ref "S2") (pin "2") (pinfunction "2_2") (pintype "passive"))
      (node (ref "SW2") (pin "RIGHT") (pinfunction "S_RIGHT") (pintype "passive"))
    )
    (net (code "69") (name "Net-(SW3-O)") (class "Default")
      (node (ref "R25") (pin "1") (pinfunction "1_1") (pintype "passive"))
      (node (ref "SW3") (pin "LEFT") (pinfunction "O_LEFT") (pintype "passive"))
    )
    (net (code "70") (name "Net-(SW3-S)") (class "Default")
      (node (ref "R21") (pin "1") (pinfunction "1_1") (pintype "passive"))
      (node (ref "S3") (pin "1") (pinfunction "1_1") (pintype "passive"))
      (node (ref "S3") (pin "2") (pinfunction "2_2") (pintype "passive"))
      (node (ref "SW3") (pin "RIGHT") (pinfunction "S_RIGHT") (pintype "passive"))
    )
    (net (code "71") (name "Net-(SW4-O)") (class "Default")
      (node (ref "R26") (pin "1") (pinfunction "1_1") (pintype "passive"))
      (node (ref "SW4") (pin "LEFT") (pinfunction "O_LEFT") (pintype "passive"))
    )
    (net (code "72") (name "Net-(SW4-S)") (class "Default")
      (node (ref "R20") (pin "1") (pinfunction "1_1") (pintype "passive"))
      (node (ref "S4") (pin "1") (pinfunction "1_1") (pintype "passive"))
      (node (ref "S4") (pin "2") (pinfunction "2_2") (pintype "passive"))
      (node (ref "SW4") (pin "RIGHT") (pinfunction "S_RIGHT") (pintype "passive"))
    )
    (net (code "73") (name "Net-(SW5-O)") (class "Default")
      (node (ref "R27") (pin "1") (pinfunction "1_1") (pintype "passive"))
      (node (ref "SW5") (pin "LEFT") (pinfunction "O_LEFT") (pintype "passive"))
    )
    (net (code "74") (name "Net-(SW5-S)") (class "Default")
      (node (ref "R19") (pin "1") (pinfunction "1_1") (pintype "passive"))
      (node (ref "S5") (pin "1") (pinfunction "1_1") (pintype "passive"))
      (node (ref "S5") (pin "2") (pinfunction "2_2") (pintype "passive"))
      (node (ref "SW5") (pin "RIGHT") (pinfunction "S_RIGHT") (pintype "passive"))
    )
    (net (code "75") (name "Net-(SW6-O)") (class "Default")
      (node (ref "R28") (pin "1") (pinfunction "1_1") (pintype "passive"))
      (node (ref "SW6") (pin "LEFT") (pinfunction "O_LEFT") (pintype "passive"))
    )
    (net (code "76") (name "Net-(SW6-S)") (class "Default")
      (node (ref "R18") (pin "1") (pinfunction "1_1") (pintype "passive"))
      (node (ref "SW6") (pin "RIGHT") (pinfunction "S_RIGHT") (pintype "passive"))
    )
    (net (code "77") (name "SW1") (class "Default")
      (node (ref "IC1") (pin "51") (pinfunction "B1/50_51") (pintype "bidirectional"))
      (node (ref "JP12") (pin "13") (pinfunction "13_13") (pintype "passive"))
      (node (ref "JP4") (pin "1") (pinfunction "1_1") (pintype "passive"))
      (node (ref "R6") (pin "1") (pinfunction "1_1") (pintype "passive"))
      (node (ref "S1") (pin "3") (pinfunction "3_3") (pintype "passive"))
      (node (ref "S1") (pin "4") (pinfunction "4_4") (pintype "passive"))
      (node (ref "SW1") (pin "COMMON") (pinfunction "P_COMMON") (pintype "passive"))
    )
    (net (code "78") (name "SW2") (class "Default")
      (node (ref "IC1") (pin "50") (pinfunction "B1/49_50") (pintype "bidirectional"))
      (node (ref "JP12") (pin "14") (pinfunction "14_14") (pintype "passive"))
      (node (ref "JP4") (pin "2") (pinfunction "2_2") (pintype "passive"))
      (node (ref "R7") (pin "1") (pinfunction "1_1") (pintype "passive"))
      (node (ref "S2") (pin "3") (pinfunction "3_3") (pintype "passive"))
      (node (ref "S2") (pin "4") (pinfunction "4_4") (pintype "passive"))
      (node (ref "SW2") (pin "COMMON") (pinfunction "P_COMMON") (pintype "passive"))
    )
    (net (code "79") (name "SW3") (class "Default")
      (node (ref "IC1") (pin "49") (pinfunction "B1/48_49") (pintype "bidirectional"))
      (node (ref "JP12") (pin "15") (pinfunction "15_15") (pintype "passive"))
      (node (ref "JP4") (pin "3") (pinfunction "3_3") (pintype "passive"))
      (node (ref "R8") (pin "1") (pinfunction "1_1") (pintype "passive"))
      (node (ref "S3") (pin "3") (pinfunction "3_3") (pintype "passive"))
      (node (ref "S3") (pin "4") (pinfunction "4_4") (pintype "passive"))
      (node (ref "SW3") (pin "COMMON") (pinfunction "P_COMMON") (pintype "passive"))
    )
    (net (code "80") (name "SW4") (class "Default")
      (node (ref "IC1") (pin "48") (pinfunction "B1/47_48") (pintype "bidirectional"))
      (node (ref "JP12") (pin "16") (pinfunction "16_16") (pintype "passive"))
      (node (ref "JP4") (pin "4") (pinfunction "4_4") (pintype "passive"))
      (node (ref "R9") (pin "1") (pinfunction "1_1") (pintype "passive"))
      (node (ref "S4") (pin "3") (pinfunction "3_3") (pintype "passive"))
      (node (ref "S4") (pin "4") (pinfunction "4_4") (pintype "passive"))
      (node (ref "SW4") (pin "COMMON") (pinfunction "P_COMMON") (pintype "passive"))
    )
    (net (code "81") (name "SW5") (class "Default")
      (node (ref "IC1") (pin "47") (pinfunction "B1/46_47") (pintype "bidirectional"))
      (node (ref "JP12") (pin "17") (pinfunction "17_17") (pintype "passive"))
      (node (ref "JP4") (pin "5") (pinfunction "5_5") (pintype "passive"))
      (node (ref "R10") (pin "1") (pinfunction "1_1") (pintype "passive"))
      (node (ref "S5") (pin "3") (pinfunction "3_3") (pintype "passive"))
      (node (ref "S5") (pin "4") (pinfunction "4_4") (pintype "passive"))
      (node (ref "SW5") (pin "COMMON") (pinfunction "P_COMMON") (pintype "passive"))
    )
    (net (code "82") (name "unconnected-(H1-MOUNT-PadB3,3)") (class "Default")
      (node (ref "H1") (pin "B3,3") (pinfunction "MOUNT_B3,3") (pintype "passive"))
    )
    (net (code "83") (name "unconnected-(H2-MOUNT-PadB3,3)") (class "Default")
      (node (ref "H2") (pin "B3,3") (pinfunction "MOUNT_B3,3") (pintype "passive"))
    )
    (net (code "84") (name "unconnected-(H3-MOUNT-PadB3,3)") (class "Default")
      (node (ref "H3") (pin "B3,3") (pinfunction "MOUNT_B3,3") (pintype "passive"))
    )
    (net (code "85") (name "unconnected-(H4-MOUNT-PadB3,3)") (class "Default")
      (node (ref "H4") (pin "B3,3") (pinfunction "MOUNT_B3,3") (pintype "passive"))
    )
    (net (code "86") (name "unconnected-(IC1-B1{slash}13-Pad15)") (class "Default")
      (node (ref "IC1") (pin "15") (pinfunction "B1/13_15") (pintype "bidirectional"))
    )
    (net (code "87") (name "unconnected-(IC1-B1{slash}14-Pad16)") (class "Default")
      (node (ref "IC1") (pin "16") (pinfunction "B1/14_16") (pintype "bidirectional"))
    )
    (net (code "88") (name "unconnected-(IC1-B1{slash}15-Pad17)") (class "Default")
      (node (ref "IC1") (pin "17") (pinfunction "B1/15_17") (pintype "bidirectional"))
    )
    (net (code "89") (name "unconnected-(IC1-B1{slash}16-Pad18)") (class "Default")
      (node (ref "IC1") (pin "18") (pinfunction "B1/16_18") (pintype "bidirectional"))
    )
    (net (code "90") (name "unconnected-(IC1-B1{slash}17-Pad19)") (class "Default")
      (node (ref "IC1") (pin "19") (pinfunction "B1/17_19") (pintype "bidirectional"))
    )
    (net (code "91") (name "unconnected-(IC1-B1{slash}18-Pad20)") (class "Default")
      (node (ref "IC1") (pin "20") (pinfunction "B1/18_20") (pintype "bidirectional"))
    )
    (net (code "92") (name "unconnected-(IC1-B1{slash}34-Pad35)") (class "Default")
      (node (ref "IC1") (pin "35") (pinfunction "B1/34_35") (pintype "bidirectional"))
    )
    (net (code "93") (name "unconnected-(IC1-B1{slash}35-Pad36)") (class "Default")
      (node (ref "IC1") (pin "36") (pinfunction "B1/35_36") (pintype "bidirectional"))
    )
    (net (code "94") (name "unconnected-(IC1-B1{slash}36-Pad37)") (class "Default")
      (node (ref "IC1") (pin "37") (pinfunction "B1/36_37") (pintype "bidirectional"))
    )
    (net (code "95") (name "unconnected-(IC1-B1{slash}37-Pad38)") (class "Default")
      (node (ref "IC1") (pin "38") (pinfunction "B1/37_38") (pintype "bidirectional"))
    )
    (net (code "96") (name "unconnected-(IC1-B1{slash}38-Pad39)") (class "Default")
      (node (ref "IC1") (pin "39") (pinfunction "B1/38_39") (pintype "bidirectional"))
    )
    (net (code "97") (name "unconnected-(IC1-B1{slash}39-Pad40)") (class "Default")
      (node (ref "IC1") (pin "40") (pinfunction "B1/39_40") (pintype "bidirectional"))
    )
    (net (code "98") (name "unconnected-(IC1-B1{slash}40-Pad41)") (class "Default")
      (node (ref "IC1") (pin "41") (pinfunction "B1/40_41") (pintype "bidirectional"))
    )
    (net (code "99") (name "unconnected-(IC1-B1{slash}41-Pad42)") (class "Default")
      (node (ref "IC1") (pin "42") (pinfunction "B1/41_42") (pintype "bidirectional"))
    )
    (net (code "100") (name "unconnected-(IC1-B1{slash}43-DEV_CLRN-Pad44)") (class "Default")
      (node (ref "IC1") (pin "44") (pinfunction "B1/43-DEV_CLRN_44") (pintype "bidirectional"))
    )
    (net (code "101") (name "unconnected-(IC1-B2{slash}51-Pad52)") (class "Default")
      (node (ref "IC1") (pin "52") (pinfunction "B2/51_52") (pintype "bidirectional"))
    )
    (net (code "102") (name "unconnected-(IC1-B2{slash}52-Pad53)") (class "Default")
      (node (ref "IC1") (pin "53") (pinfunction "B2/52_53") (pintype "bidirectional"))
    )
    (net (code "103") (name "unconnected-(IC1-B2{slash}53-Pad54)") (class "Default")
      (node (ref "IC1") (pin "54") (pinfunction "B2/53_54") (pintype "bidirectional"))
    )
    (net (code "104") (name "unconnected-(IC1-B2{slash}54-Pad55)") (class "Default")
      (node (ref "IC1") (pin "55") (pinfunction "B2/54_55") (pintype "bidirectional"))
    )
    (net (code "105") (name "unconnected-(IC1-B2{slash}55-Pad56)") (class "Default")
      (node (ref "IC1") (pin "56") (pinfunction "B2/55_56") (pintype "bidirectional"))
    )
    (net (code "106") (name "unconnected-(IC1-B2{slash}56-Pad57)") (class "Default")
      (node (ref "IC1") (pin "57") (pinfunction "B2/56_57") (pintype "bidirectional"))
    )
    (net (code "107") (name "unconnected-(IC1-B2{slash}57-Pad58)") (class "Default")
      (node (ref "IC1") (pin "58") (pinfunction "B2/57_58") (pintype "bidirectional"))
    )
    (net (code "108") (name "unconnected-(IC1-B2{slash}60-Pad61)") (class "Default")
      (node (ref "IC1") (pin "61") (pinfunction "B2/60_61") (pintype "bidirectional"))
    )
    (net (code "109") (name "unconnected-(IC1-B2{slash}61-GCLK2-Pad62)") (class "Default")
      (node (ref "IC1") (pin "62") (pinfunction "B2/61-GCLK2_62") (pintype "bidirectional"))
    )
    (net (code "110") (name "unconnected-(IC1-B2{slash}63-GCLK3-Pad64)") (class "Default")
      (node (ref "IC1") (pin "64") (pinfunction "B2/63-GCLK3_64") (pintype "bidirectional"))
    )
    (net (code "111") (name "unconnected-(IC1-B2{slash}75-Pad76)") (class "Default")
      (node (ref "IC1") (pin "76") (pinfunction "B2/75_76") (pintype "bidirectional"))
    )
    (net (code "112") (name "unconnected-(IC1-B2{slash}76-Pad77)") (class "Default")
      (node (ref "IC1") (pin "77") (pinfunction "B2/76_77") (pintype "bidirectional"))
    )
    (net (code "113") (name "unconnected-(IC1-B2{slash}77-Pad78)") (class "Default")
      (node (ref "IC1") (pin "78") (pinfunction "B2/77_78") (pintype "bidirectional"))
    )
    (net (code "114") (name "unconnected-(IC1-B2{slash}80-Pad81)") (class "Default")
      (node (ref "IC1") (pin "81") (pinfunction "B2/80_81") (pintype "bidirectional"))
    )
    (net (code "115") (name "unconnected-(IC1-B2{slash}81-Pad82)") (class "Default")
      (node (ref "IC1") (pin "82") (pinfunction "B2/81_82") (pintype "bidirectional"))
    )
    (net (code "116") (name "unconnected-(IC1-B2{slash}82-Pad83)") (class "Default")
      (node (ref "IC1") (pin "83") (pinfunction "B2/82_83") (pintype "bidirectional"))
    )
    (net (code "117") (name "unconnected-(IC1-B2{slash}83-Pad84)") (class "Default")
      (node (ref "IC1") (pin "84") (pinfunction "B2/83_84") (pintype "bidirectional"))
    )
    (net (code "118") (name "unconnected-(IC1-B2{slash}84-Pad85)") (class "Default")
      (node (ref "IC1") (pin "85") (pinfunction "B2/84_85") (pintype "bidirectional"))
    )
    (net (code "119") (name "unconnected-(IC1-B2{slash}85-Pad86)") (class "Default")
      (node (ref "IC1") (pin "86") (pinfunction "B2/85_86") (pintype "bidirectional"))
    )
    (net (code "120") (name "unconnected-(IC1-B2{slash}86-Pad87)") (class "Default")
      (node (ref "IC1") (pin "87") (pinfunction "B2/86_87") (pintype "bidirectional"))
    )
    (net (code "121") (name "unconnected-(IC1-B2{slash}87-Pad88)") (class "Default")
      (node (ref "IC1") (pin "88") (pinfunction "B2/87_88") (pintype "bidirectional"))
    )
    (net (code "122") (name "unconnected-(IC1-B2{slash}88-Pad89)") (class "Default")
      (node (ref "IC1") (pin "89") (pinfunction "B2/88_89") (pintype "bidirectional"))
    )
    (net (code "123") (name "unconnected-(IC1-B2{slash}89-Pad90)") (class "Default")
      (node (ref "IC1") (pin "90") (pinfunction "B2/89_90") (pintype "bidirectional"))
    )
    (net (code "124") (name "unconnected-(IC1-B2{slash}90-Pad91)") (class "Default")
      (node (ref "IC1") (pin "91") (pinfunction "B2/90_91") (pintype "bidirectional"))
    )
    (net (code "125") (name "unconnected-(IC1-B2{slash}91-Pad92)") (class "Default")
      (node (ref "IC1") (pin "92") (pinfunction "B2/91_92") (pintype "bidirectional"))
    )
    (net (code "126") (name "unconnected-(IC1-B2{slash}94-Pad95)") (class "Default")
      (node (ref "IC1") (pin "95") (pinfunction "B2/94_95") (pintype "bidirectional"))
    )
    (net (code "127") (name "unconnected-(IC1-B2{slash}95-Pad96)") (class "Default")
      (node (ref "IC1") (pin "96") (pinfunction "B2/95_96") (pintype "bidirectional"))
    )
    (net (code "128") (name "unconnected-(IC1-B2{slash}96-Pad97)") (class "Default")
      (node (ref "IC1") (pin "97") (pinfunction "B2/96_97") (pintype "bidirectional"))
    )
    (net (code "129") (name "unconnected-(IC1-B2{slash}97-Pad98)") (class "Default")
      (node (ref "IC1") (pin "98") (pinfunction "B2/97_98") (pintype "bidirectional"))
    )
    (net (code "130") (name "unconnected-(IC1-B2{slash}98-Pad99)") (class "Default")
      (node (ref "IC1") (pin "99") (pinfunction "B2/98_99") (pintype "bidirectional"))
    )
    (net (code "131") (name "unconnected-(IC1-B2{slash}99-Pad100)") (class "Default")
      (node (ref "IC1") (pin "100") (pinfunction "B2/99_100") (pintype "bidirectional"))
    )
    (net (code "132") (name "unconnected-(IC2-RB5{slash}RX-Pad12)") (class "Default")
      (node (ref "IC2") (pin "12") (pinfunction "RB5/RX_12") (pintype "bidirectional"))
    )
    (net (code "133") (name "unconnected-(IC2-RC3{slash}AN7-Pad7)") (class "Default")
      (node (ref "IC2") (pin "7") (pinfunction "RC3/AN7_7") (pintype "bidirectional"))
    )
    (net (code "134") (name "unconnected-(IC2-RC6{slash}AN8-Pad8)") (class "Default")
      (node (ref "IC2") (pin "8") (pinfunction "RC6/AN8_8") (pintype "bidirectional"))
    )
    (net (code "135") (name "unconnected-(IC3-VI-Pad2)") (class "Default")
      (node (ref "IC3") (pin "2") (pinfunction "VI_2") (pintype "input"))
    )
    (net (code "136") (name "unconnected-(J8-ID-Pad4)") (class "Default")
      (node (ref "J8") (pin "4") (pinfunction "ID_4") (pintype "bidirectional"))
    )
  )
)
